# Memory_SRAM.net
KiCad netlist of a schematic drawn in Altium Designer
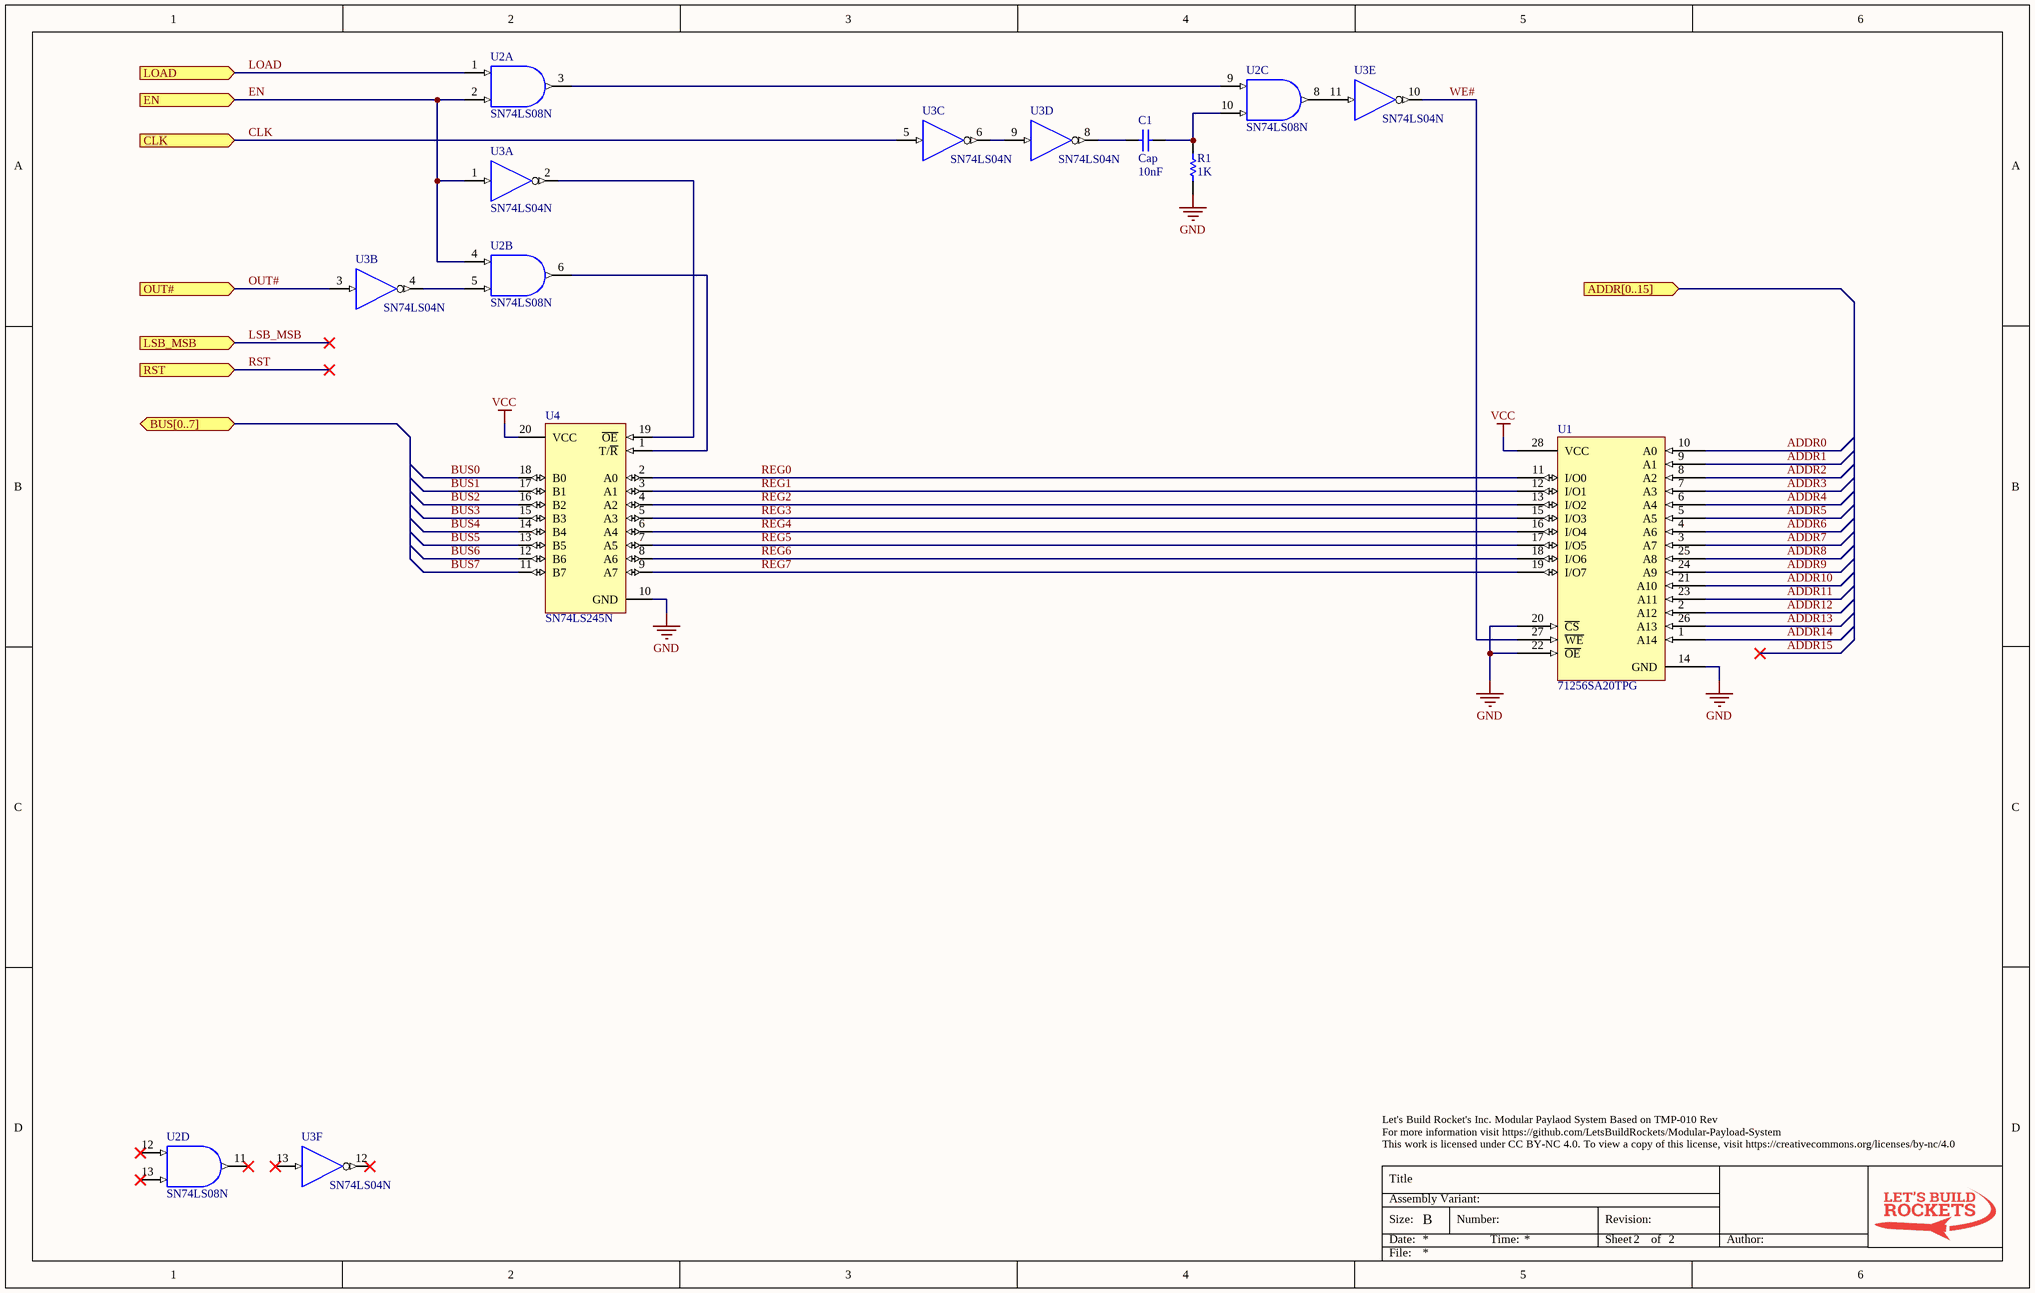
[diagram p0: Memory_SRAM.SchDoc]

(export (version "E")
  (design (tool "Eeschema 10.0.6"))
  (components
    (comp (ref "C1")
      (value "Cap")
      (footprint "RAD-0.3")
      (description "Capacitor")
      (fields (field (name "ALTIUM_VALUE") "10nF") (field (name "PUBLISHER") "Altium Limited"))
      (libsource (lib "Miscellaneous Devices") (part "Cap"))
    )
    (comp (ref "R1")
      (value "1K")
      (footprint "AXIAL-0.3")
      (description "Resistor")
      (fields (field (name "Comment") "Res1") (field (name "PUBLISHER") "Altium Limited"))
      (libsource (lib "Miscellaneous Devices") (part "Res1"))
    )
    (comp (ref "U1")
      (value "71256SA20TPG")
      (footprint "JT028")
      (libsource (lib "Schlib1") (part "71256SA20TPG"))
    )
    (comp (ref "U2")
      (value "SN74LS08N")
      (footprint "N014")
      (description "Quadruple 2-Input Positive-AND Gate")
      (fields (field (name "PUBLISHER") "Altium Limited"))
      (libsource (lib "TI Logic Gate 2") (part "SN74LS08N"))
    )
    (comp (ref "U3")
      (value "SN74LS04N")
      (footprint "N014")
      (description "Hex Inverter")
      (fields (field (name "PUBLISHER") "Altium Limited"))
      (libsource (lib "TI Logic Gate 2") (part "SN74LS04N"))
    )
    (comp (ref "U4")
      (value "SN74LS245N")
      (footprint "N020")
      (description "Octal Bus Transceiver with 3-State Outputs")
      (fields (field (name "PUBLISHER") "Altium Limited"))
      (libsource (lib "TI Interface 8-Bit Line Transceiver") (part "SN74LS245N"))
    )
  )
  (nets
    (net (code "1") (name "/ADDR0") (class "Default")
      (node (ref "U1") (pin "10") (pinfunction "A0_10") (pintype "input"))
    )
    (net (code "2") (name "/ADDR1") (class "Default")
      (node (ref "U1") (pin "9") (pinfunction "A1_9") (pintype "input"))
    )
    (net (code "3") (name "/ADDR2") (class "Default")
      (node (ref "U1") (pin "8") (pinfunction "A2_8") (pintype "input"))
    )
    (net (code "4") (name "/ADDR3") (class "Default")
      (node (ref "U1") (pin "7") (pinfunction "A3_7") (pintype "input"))
    )
    (net (code "5") (name "/ADDR4") (class "Default")
      (node (ref "U1") (pin "6") (pinfunction "A4_6") (pintype "input"))
    )
    (net (code "6") (name "/ADDR5") (class "Default")
      (node (ref "U1") (pin "5") (pinfunction "A5_5") (pintype "input"))
    )
    (net (code "7") (name "/ADDR6") (class "Default")
      (node (ref "U1") (pin "4") (pinfunction "A6_4") (pintype "input"))
    )
    (net (code "8") (name "/ADDR7") (class "Default")
      (node (ref "U1") (pin "3") (pinfunction "A7_3") (pintype "input"))
    )
    (net (code "9") (name "/ADDR8") (class "Default")
      (node (ref "U1") (pin "25") (pinfunction "A8_25") (pintype "input"))
    )
    (net (code "10") (name "/ADDR9") (class "Default")
      (node (ref "U1") (pin "24") (pinfunction "A9_24") (pintype "input"))
    )
    (net (code "11") (name "/ADDR10") (class "Default")
      (node (ref "U1") (pin "21") (pinfunction "A10_21") (pintype "input"))
    )
    (net (code "12") (name "/ADDR11") (class "Default")
      (node (ref "U1") (pin "23") (pinfunction "A11_23") (pintype "input"))
    )
    (net (code "13") (name "/ADDR12") (class "Default")
      (node (ref "U1") (pin "2") (pinfunction "A12_2") (pintype "input"))
    )
    (net (code "14") (name "/ADDR13") (class "Default")
      (node (ref "U1") (pin "26") (pinfunction "A13_26") (pintype "input"))
    )
    (net (code "15") (name "/ADDR14") (class "Default")
      (node (ref "U1") (pin "1") (pinfunction "A14_1") (pintype "input"))
    )
    (net (code "18") (name "/BUS0") (class "Default")
      (node (ref "U4") (pin "18") (pinfunction "B0_18") (pintype "bidirectional"))
    )
    (net (code "19") (name "/BUS1") (class "Default")
      (node (ref "U4") (pin "17") (pinfunction "B1_17") (pintype "bidirectional"))
    )
    (net (code "20") (name "/BUS2") (class "Default")
      (node (ref "U4") (pin "16") (pinfunction "B2_16") (pintype "bidirectional"))
    )
    (net (code "21") (name "/BUS3") (class "Default")
      (node (ref "U4") (pin "15") (pinfunction "B3_15") (pintype "bidirectional"))
    )
    (net (code "22") (name "/BUS4") (class "Default")
      (node (ref "U4") (pin "14") (pinfunction "B4_14") (pintype "bidirectional"))
    )
    (net (code "23") (name "/BUS5") (class "Default")
      (node (ref "U4") (pin "13") (pinfunction "B5_13") (pintype "bidirectional"))
    )
    (net (code "24") (name "/BUS6") (class "Default")
      (node (ref "U4") (pin "12") (pinfunction "B6_12") (pintype "bidirectional"))
    )
    (net (code "25") (name "/BUS7") (class "Default")
      (node (ref "U4") (pin "11") (pinfunction "B7_11") (pintype "bidirectional"))
    )
    (net (code "27") (name "/CLK") (class "Default")
      (node (ref "U3") (pin "5") (pinfunction "A_5") (pintype "input"))
    )
    (net (code "28") (name "/EN") (class "Default")
      (node (ref "U2") (pin "2") (pinfunction "B_2") (pintype "input"))
      (node (ref "U2") (pin "4") (pinfunction "A_4") (pintype "input"))
      (node (ref "U3") (pin "1") (pinfunction "A_1") (pintype "input"))
    )
    (net (code "29") (name "/LOAD") (class "Default")
      (node (ref "U2") (pin "1") (pinfunction "A_1") (pintype "input"))
    )
    (net (code "31") (name "/OUT#") (class "Default")
      (node (ref "U3") (pin "3") (pinfunction "A_3") (pintype "input"))
    )
    (net (code "32") (name "/REG0") (class "Default")
      (node (ref "U1") (pin "11") (pinfunction "I/O0_11") (pintype "bidirectional"))
      (node (ref "U4") (pin "2") (pinfunction "A0_2") (pintype "bidirectional"))
    )
    (net (code "33") (name "/REG1") (class "Default")
      (node (ref "U1") (pin "12") (pinfunction "I/O1_12") (pintype "bidirectional"))
      (node (ref "U4") (pin "3") (pinfunction "A1_3") (pintype "bidirectional"))
    )
    (net (code "34") (name "/REG2") (class "Default")
      (node (ref "U1") (pin "13") (pinfunction "I/O2_13") (pintype "bidirectional"))
      (node (ref "U4") (pin "4") (pinfunction "A2_4") (pintype "bidirectional"))
    )
    (net (code "35") (name "/REG3") (class "Default")
      (node (ref "U1") (pin "15") (pinfunction "I/O3_15") (pintype "bidirectional"))
      (node (ref "U4") (pin "5") (pinfunction "A3_5") (pintype "bidirectional"))
    )
    (net (code "36") (name "/REG4") (class "Default")
      (node (ref "U1") (pin "16") (pinfunction "I/O4_16") (pintype "bidirectional"))
      (node (ref "U4") (pin "6") (pinfunction "A4_6") (pintype "bidirectional"))
    )
    (net (code "37") (name "/REG5") (class "Default")
      (node (ref "U1") (pin "17") (pinfunction "I/O5_17") (pintype "bidirectional"))
      (node (ref "U4") (pin "7") (pinfunction "A5_7") (pintype "bidirectional"))
    )
    (net (code "38") (name "/REG6") (class "Default")
      (node (ref "U1") (pin "18") (pinfunction "I/O6_18") (pintype "bidirectional"))
      (node (ref "U4") (pin "8") (pinfunction "A6_8") (pintype "bidirectional"))
    )
    (net (code "39") (name "/REG7") (class "Default")
      (node (ref "U1") (pin "19") (pinfunction "I/O7_19") (pintype "bidirectional"))
      (node (ref "U4") (pin "9") (pinfunction "A7_9") (pintype "bidirectional"))
    )
    (net (code "41") (name "/WE#") (class "Default")
      (node (ref "U1") (pin "27") (pinfunction "~{WE}_27") (pintype "input"))
      (node (ref "U3") (pin "10") (pinfunction "Y_10") (pintype "output"))
    )
    (net (code "42") (name "GND") (class "Default")
      (node (ref "R1") (pin "1") (pinfunction "1_1") (pintype "passive"))
      (node (ref "U1") (pin "14") (pinfunction "GND_14") (pintype "power_in"))
      (node (ref "U1") (pin "20") (pinfunction "~{CS}_20") (pintype "input"))
      (node (ref "U1") (pin "22") (pinfunction "~{OE}_22") (pintype "input"))
      (node (ref "U2") (pin "7") (pinfunction "GND_7") (pintype "power_in"))
      (node (ref "U3") (pin "7") (pinfunction "GND_7") (pintype "power_in"))
      (node (ref "U4") (pin "10") (pinfunction "GND_10") (pintype "power_in"))
    )
    (net (code "43") (name "Net-(U2A-Y)") (class "Default")
      (node (ref "U2") (pin "3") (pinfunction "Y_3") (pintype "output"))
      (node (ref "U2") (pin "9") (pinfunction "A_9") (pintype "input"))
    )
    (net (code "44") (name "Net-(U2B-B)") (class "Default")
      (node (ref "U2") (pin "5") (pinfunction "B_5") (pintype "input"))
      (node (ref "U3") (pin "4") (pinfunction "Y_4") (pintype "output"))
    )
    (net (code "45") (name "Net-(U2B-Y)") (class "Default")
      (node (ref "U2") (pin "6") (pinfunction "Y_6") (pintype "output"))
      (node (ref "U4") (pin "1") (pinfunction "T/~{R}_1") (pintype "input"))
    )
    (net (code "46") (name "Net-(U2C-B)") (class "Default")
      (node (ref "C1") (pin "1") (pinfunction "1_1") (pintype "passive"))
      (node (ref "R1") (pin "2") (pinfunction "2_2") (pintype "passive"))
      (node (ref "U2") (pin "10") (pinfunction "B_10") (pintype "input"))
    )
    (net (code "47") (name "Net-(U2C-Y)") (class "Default")
      (node (ref "U2") (pin "8") (pinfunction "Y_8") (pintype "output"))
      (node (ref "U3") (pin "11") (pinfunction "A_11") (pintype "input"))
    )
    (net (code "48") (name "Net-(U3A-Y)") (class "Default")
      (node (ref "U3") (pin "2") (pinfunction "Y_2") (pintype "output"))
      (node (ref "U4") (pin "19") (pinfunction "~{OE}_19") (pintype "input"))
    )
    (net (code "49") (name "Net-(U3C-Y)") (class "Default")
      (node (ref "U3") (pin "6") (pinfunction "Y_6") (pintype "output"))
      (node (ref "U3") (pin "9") (pinfunction "A_9") (pintype "input"))
    )
    (net (code "50") (name "Net-(U3D-Y)") (class "Default")
      (node (ref "C1") (pin "2") (pinfunction "2_2") (pintype "passive"))
      (node (ref "U3") (pin "8") (pinfunction "Y_8") (pintype "output"))
    )
    (net (code "51") (name "VCC") (class "Default")
      (node (ref "U1") (pin "28") (pinfunction "VCC_28") (pintype "power_in"))
      (node (ref "U2") (pin "14") (pinfunction "VCC_14") (pintype "power_in"))
      (node (ref "U3") (pin "14") (pinfunction "VCC_14") (pintype "power_in"))
      (node (ref "U4") (pin "20") (pinfunction "VCC_20") (pintype "power_in"))
    )
    (net (code "52") (name "unconnected-(U2D-A-Pad12)") (class "Default")
      (node (ref "U2") (pin "12") (pinfunction "A_12") (pintype "input+no_connect"))
    )
    (net (code "53") (name "unconnected-(U2D-B-Pad13)") (class "Default")
      (node (ref "U2") (pin "13") (pinfunction "B_13") (pintype "input+no_connect"))
    )
    (net (code "54") (name "unconnected-(U2D-Y-Pad11)") (class "Default")
      (node (ref "U2") (pin "11") (pinfunction "Y_11") (pintype "output+no_connect"))
    )
    (net (code "55") (name "unconnected-(U3F-A-Pad13)") (class "Default")
      (node (ref "U3") (pin "13") (pinfunction "A_13") (pintype "input+no_connect"))
    )
    (net (code "56") (name "unconnected-(U3F-Y-Pad12)") (class "Default")
      (node (ref "U3") (pin "12") (pinfunction "Y_12") (pintype "output+no_connect"))
    )
  )
)
